# Blind_Spot_Detector.net
KiCad netlist of a schematic drawn in EAGLE
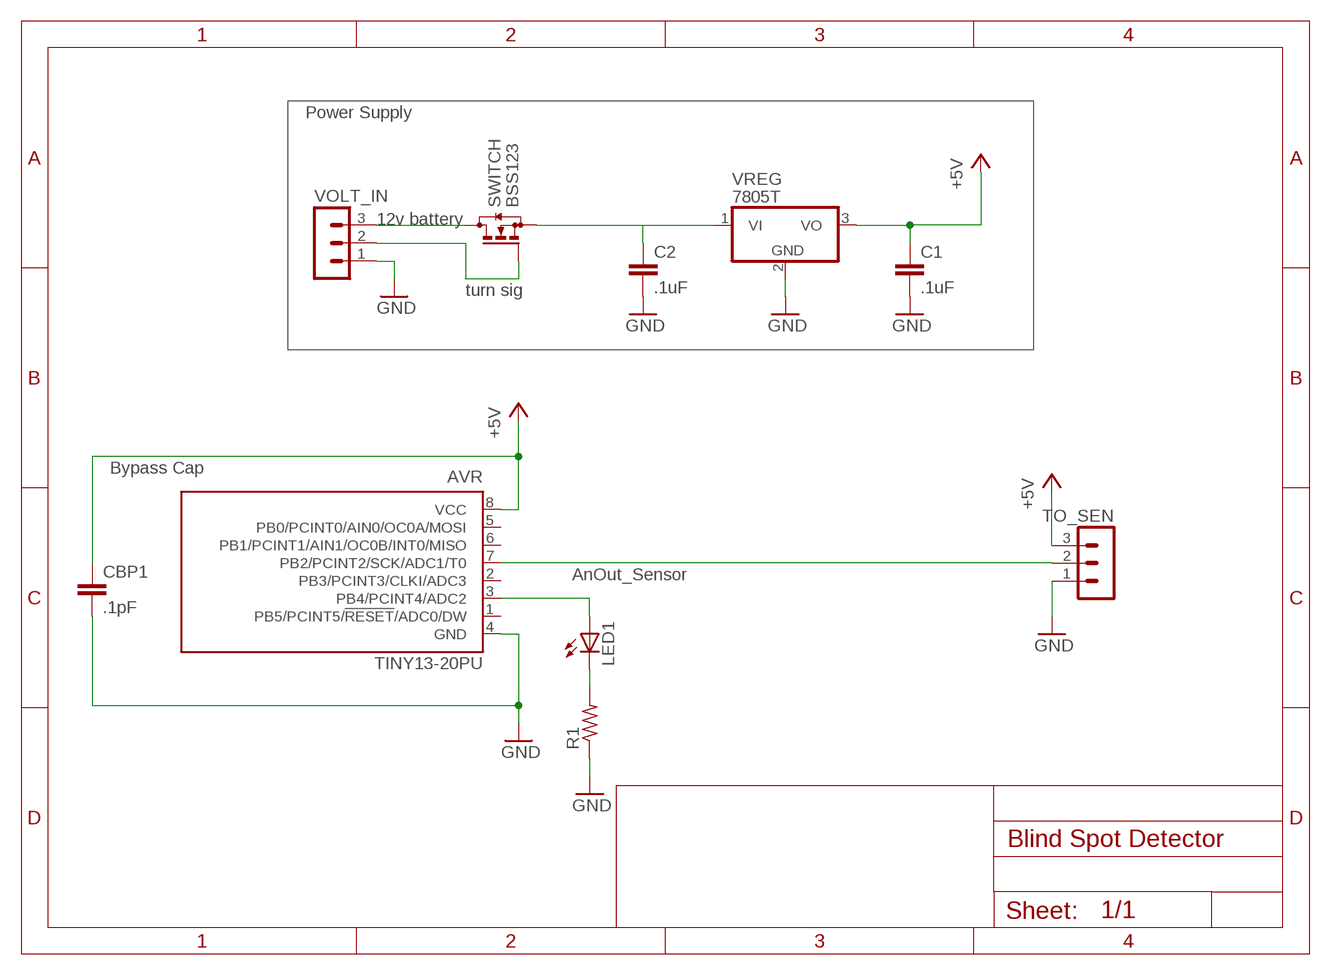
[diagram p0: schematic, sheet 1]

(export (version "E")
  (design (tool "Eeschema 10.0.6"))
  (components
    (comp (ref "AVR")
      (value "TINY13-20PU")
      (footprint "eagle-import:DIL08")
      (fields (field (name "MPN") "ATTINY13-20PU"))
      (libsource (lib "eagle-import") (part "TINY13PU-20"))
    )
    (comp (ref "C1")
      (value ".1uF")
      (footprint "eagle-import:C0805")
      (libsource (lib "eagle-import") (part "C-EUC0805"))
    )
    (comp (ref "C2")
      (value ".1uF")
      (footprint "eagle-import:C0805")
      (libsource (lib "eagle-import") (part "C-EUC0805"))
    )
    (comp (ref "CBP1")
      (value ".1pF")
      (footprint "eagle-import:C0805")
      (libsource (lib "eagle-import") (part "C-EUC0805"))
    )
    (comp (ref "LED1")
      (value "LED5MM")
      (footprint "eagle-import:LED5MM")
      (libsource (lib "eagle-import") (part "LED5MM"))
    )
    (comp (ref "R1")
      (value "R-US_R0805")
      (footprint "eagle-import:R0805")
      (libsource (lib "eagle-import") (part "R-US_R0805"))
    )
    (comp (ref "SWITCH")
      (value "BSS123")
      (footprint "eagle-import:SOT23")
      (libsource (lib "eagle-import") (part "BSS123"))
    )
    (comp (ref "TO_SEN")
      (value "MA03-1")
      (footprint "eagle-import:MA03-1")
      (libsource (lib "eagle-import") (part "MA03-1"))
    )
    (comp (ref "VOLT_IN")
      (value "MA03-1")
      (footprint "eagle-import:MA03-1")
      (libsource (lib "eagle-import") (part "MA03-1"))
    )
    (comp (ref "VREG")
      (value "7805T")
      (footprint "eagle-import:TO220H")
      (libsource (lib "eagle-import") (part "78T05"))
    )
  )
  (nets
    (net (code "1") (name "+5V") (class "Default")
      (node (ref "AVR") (pin "8") (pinfunction "VCC_8") (pintype "power_in"))
      (node (ref "C1") (pin "1") (pinfunction "1_1") (pintype "passive"))
      (node (ref "CBP1") (pin "1") (pinfunction "1_1") (pintype "passive"))
      (node (ref "TO_SEN") (pin "3") (pinfunction "3_3") (pintype "passive"))
      (node (ref "VREG") (pin "3") (pinfunction "VO_3") (pintype "passive"))
    )
    (net (code "2") (name "GND") (class "Default")
      (node (ref "AVR") (pin "4") (pinfunction "GND_4") (pintype "power_in"))
      (node (ref "C1") (pin "2") (pinfunction "2_2") (pintype "passive"))
      (node (ref "C2") (pin "2") (pinfunction "2_2") (pintype "passive"))
      (node (ref "CBP1") (pin "2") (pinfunction "2_2") (pintype "passive"))
      (node (ref "R1") (pin "1") (pinfunction "1_1") (pintype "passive"))
      (node (ref "TO_SEN") (pin "1") (pinfunction "1_1") (pintype "passive"))
      (node (ref "VOLT_IN") (pin "1") (pinfunction "1_1") (pintype "passive"))
      (node (ref "VREG") (pin "2") (pinfunction "GND_2") (pintype "passive"))
    )
    (net (code "3") (name "Net-(AVR-PB2{slash}PCINT2{slash}SCK{slash}ADC1{slash}T0)") (class "Default")
      (node (ref "AVR") (pin "7") (pinfunction "PB2/PCINT2/SCK/ADC1/T0_7") (pintype "bidirectional"))
      (node (ref "TO_SEN") (pin "2") (pinfunction "2_2") (pintype "passive"))
    )
    (net (code "4") (name "Net-(AVR-PB4{slash}PCINT4{slash}ADC2)") (class "Default")
      (node (ref "AVR") (pin "3") (pinfunction "PB4/PCINT4/ADC2_3") (pintype "bidirectional"))
      (node (ref "LED1") (pin "A") (pinfunction "A_A") (pintype "passive"))
    )
    (net (code "5") (name "Net-(LED1-C)") (class "Default")
      (node (ref "LED1") (pin "K") (pinfunction "C_K") (pintype "passive"))
      (node (ref "R1") (pin "2") (pinfunction "2_2") (pintype "passive"))
    )
    (net (code "6") (name "Net-(SWITCH-D)") (class "Default")
      (node (ref "SWITCH") (pin "3") (pinfunction "D_3") (pintype "passive"))
      (node (ref "VOLT_IN") (pin "3") (pinfunction "3_3") (pintype "passive"))
    )
    (net (code "7") (name "Net-(SWITCH-G)") (class "Default")
      (node (ref "SWITCH") (pin "1") (pinfunction "G_1") (pintype "passive"))
      (node (ref "VOLT_IN") (pin "2") (pinfunction "2_2") (pintype "passive"))
    )
    (net (code "8") (name "Net-(SWITCH-S)") (class "Default")
      (node (ref "SWITCH") (pin "2") (pinfunction "S_2") (pintype "passive"))
      (node (ref "VREG") (pin "1") (pinfunction "VI_1") (pintype "input"))
    )
    (net (code "9") (name "unconnected-(AVR-PB0{slash}PCINT0{slash}AIN0{slash}OC0A{slash}MOSI-Pad5)") (class "Default")
      (node (ref "AVR") (pin "5") (pinfunction "PB0/PCINT0/AIN0/OC0A/MOSI_5") (pintype "bidirectional"))
    )
    (net (code "10") (name "unconnected-(AVR-PB1{slash}PCINT1{slash}AIN1{slash}OC0B{slash}INT0{slash}MISO-Pad6)") (class "Default")
      (node (ref "AVR") (pin "6") (pinfunction "PB1/PCINT1/AIN1/OC0B/INT0/MISO_6") (pintype "bidirectional"))
    )
    (net (code "11") (name "unconnected-(AVR-PB3{slash}PCINT3{slash}CLKI{slash}ADC3-Pad2)") (class "Default")
      (node (ref "AVR") (pin "2") (pinfunction "PB3/PCINT3/CLKI/ADC3_2") (pintype "bidirectional"))
    )
    (net (code "12") (name "unconnected-(AVR-PB5{slash}PCINT5{slash}~{RESET}{slash}ADC0{slash}DW-Pad1)") (class "Default")
      (node (ref "AVR") (pin "1") (pinfunction "PB5/PCINT5/~{RESET}/ADC0/DW_1") (pintype "bidirectional"))
    )
    (net (code "13") (name "unconnected-(C2-Pad1)") (class "Default")
      (node (ref "C2") (pin "1") (pinfunction "1_1") (pintype "passive"))
    )
  )
)
